# can.net
KiCad netlist of a schematic drawn in Altium Designer
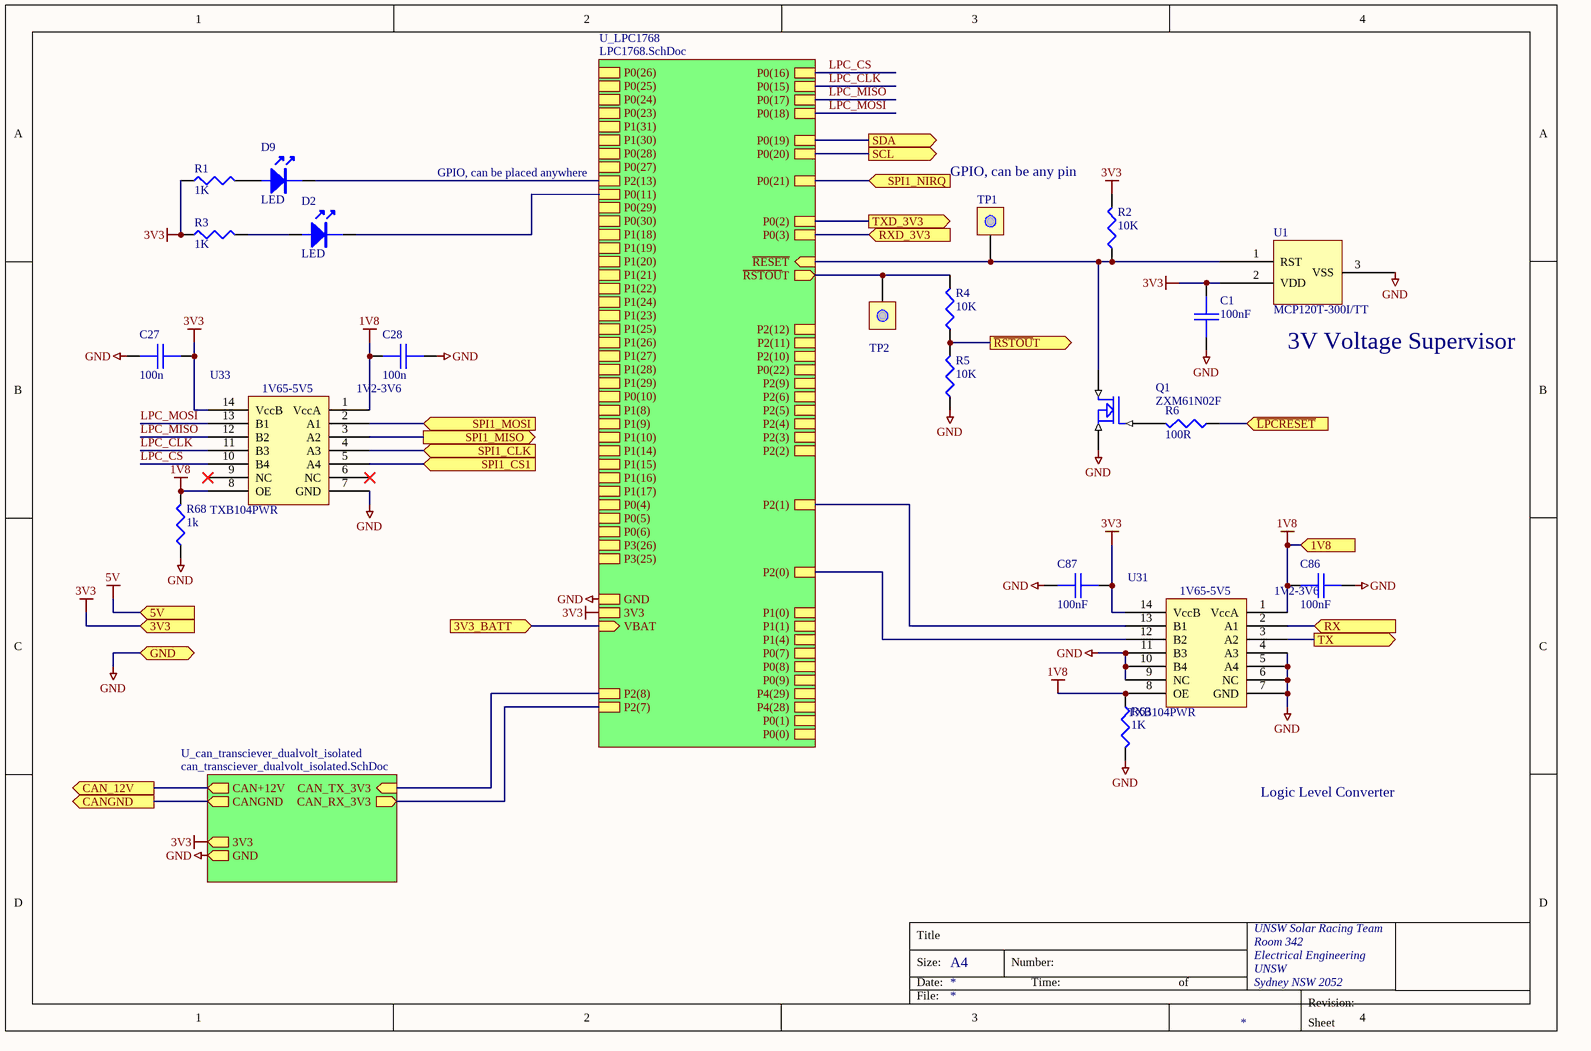
[diagram p0: can.SchDoc]

(export (version "E")
  (design (tool "Eeschema 10.0.6"))
  (components
    (comp (ref "C1")
      (value "100nF")
      (footprint "0603")
      (description "Capacitor")
      (libsource (lib "RCLDQ") (part "CAP"))
    )
    (comp (ref "C27")
      (value "100n")
      (footprint "0603")
      (description "Capacitor")
      (libsource (lib "RCLDQ") (part "CAP"))
    )
    (comp (ref "C28")
      (value "100n")
      (footprint "0603")
      (description "Capacitor")
      (libsource (lib "RCLDQ") (part "CAP"))
    )
    (comp (ref "C86")
      (value "100nF")
      (footprint "0603")
      (description "Capacitor")
      (libsource (lib "RCLDQ") (part "CAP"))
    )
    (comp (ref "C87")
      (value "100nF")
      (footprint "0603")
      (description "Capacitor")
      (libsource (lib "RCLDQ") (part "CAP"))
    )
    (comp (ref "D2") (value "LED") (footprint "0805LED") (libsource (lib "RCLDQ") (part "LED")))
    (comp (ref "D9") (value "LED") (footprint "0805LED") (libsource (lib "RCLDQ") (part "LED")))
    (comp (ref "Q1")
      (value "ZXM61N02F")
      (footprint "SOT23-3")
      (description "1.7A, 20V N-Channel Enhancement mode FET")
      (libsource (lib "RCLDQ") (part "ZXM61N02F"))
    )
    (comp (ref "R1")
      (value "1K")
      (footprint "0603")
      (description "Resistor")
      (libsource (lib "RCLDQ") (part "RES1"))
    )
    (comp (ref "R2")
      (value "10K")
      (footprint "0603")
      (description "Resistor")
      (libsource (lib "RCLDQ") (part "RES1"))
    )
    (comp (ref "R3")
      (value "1K")
      (footprint "0603")
      (description "Resistor")
      (libsource (lib "RCLDQ") (part "RES1"))
    )
    (comp (ref "R4")
      (value "10K")
      (footprint "0603")
      (description "Resistor")
      (libsource (lib "RCLDQ") (part "RES1"))
    )
    (comp (ref "R5")
      (value "10K")
      (footprint "0603")
      (description "Resistor")
      (libsource (lib "RCLDQ") (part "RES1"))
    )
    (comp (ref "R6")
      (value "100R")
      (footprint "0603")
      (description "Resistor")
      (libsource (lib "RCLDQ") (part "RES1"))
    )
    (comp (ref "R63")
      (value "1K")
      (footprint "0603")
      (description "Resistor")
      (libsource (lib "RCLDQ") (part "RES1"))
    )
    (comp (ref "R68")
      (value "1k")
      (footprint "0603")
      (description "Resistor")
      (libsource (lib "RCLDQ") (part "RES1"))
    )
    (comp (ref "TP1")
      (value "RESET")
      (footprint "TESTPOINT")
      (description "TEST POINT")
      (libsource (lib "Miscellaneous") (part "TEST"))
    )
    (comp (ref "TP2")
      (value "RSTOUT")
      (footprint "TESTPOINT")
      (description "TEST POINT")
      (libsource (lib "") (part "TEST_1"))
    )
    (comp (ref "U1")
      (value "MCP120T-300I/TT")
      (footprint "SOT23-3")
      (description "Voltage Supervisor")
      (libsource (lib "sion") (part "MCP120T"))
    )
    (comp (ref "U31")
      (value "TXB104PWR")
      (footprint "TSSOP14-L")
      (description "4 bit bidirectional auto direction sense level translator")
      (libsource (lib "sion") (part "TXB0104PWR"))
    )
    (comp (ref "U33")
      (value "TXB104PWR")
      (footprint "TSSOP14-L")
      (description "4 bit bidirectional auto direction sense level translator")
      (libsource (lib "sion") (part "TXB0104PWR"))
    )
  )
  (nets
    (net (code "6") (name "/LPC_CLK") (class "Default")
      (node (ref "U33") (pin "11") (pinfunction "B3_11") (pintype "passive"))
    )
    (net (code "7") (name "/LPC_CS") (class "Default")
      (node (ref "U33") (pin "10") (pinfunction "B4_10") (pintype "passive"))
    )
    (net (code "8") (name "/LPC_MISO") (class "Default")
      (node (ref "U33") (pin "12") (pinfunction "B2_12") (pintype "passive"))
    )
    (net (code "9") (name "/LPC_MOSI") (class "Default")
      (node (ref "U33") (pin "13") (pinfunction "B1_13") (pintype "passive"))
    )
    (net (code "19") (name "/P0(11)") (class "Default")
      (node (ref "D2") (pin "K") (pinfunction "K_K") (pintype "passive"))
    )
    (net (code "53") (name "/P2(0)") (class "Default")
      (node (ref "U31") (pin "12") (pinfunction "B2_12") (pintype "passive"))
    )
    (net (code "54") (name "/P2(1)") (class "Default")
      (node (ref "U31") (pin "13") (pinfunction "B1_13") (pintype "passive"))
    )
    (net (code "64") (name "/P2(13)") (class "Default")
      (node (ref "D9") (pin "K") (pinfunction "K_K") (pintype "passive"))
    )
    (net (code "69") (name "/RX") (class "Default")
      (node (ref "U31") (pin "2") (pinfunction "A1_2") (pintype "passive"))
    )
    (net (code "73") (name "/SPI1_CLK") (class "Default")
      (node (ref "U33") (pin "4") (pinfunction "A3_4") (pintype "passive"))
    )
    (net (code "74") (name "/SPI1_CS1") (class "Default")
      (node (ref "U33") (pin "5") (pinfunction "A4_5") (pintype "passive"))
    )
    (net (code "75") (name "/SPI1_MISO") (class "Default")
      (node (ref "U33") (pin "3") (pinfunction "A2_3") (pintype "passive"))
    )
    (net (code "76") (name "/SPI1_MOSI") (class "Default")
      (node (ref "U33") (pin "2") (pinfunction "A1_2") (pintype "passive"))
    )
    (net (code "78") (name "/TX") (class "Default")
      (node (ref "U31") (pin "3") (pinfunction "A2_3") (pintype "passive"))
    )
    (net (code "80") (name "/~{LPCRESET}") (class "Default")
      (node (ref "R6") (pin "2") (pinfunction "2_2") (pintype "passive"))
    )
    (net (code "81") (name "/~{RESET}") (class "Default")
      (node (ref "Q1") (pin "3") (pinfunction "D_3") (pintype "input"))
      (node (ref "R2") (pin "1") (pinfunction "1_1") (pintype "passive"))
      (node (ref "TP1") (pin "0") (pinfunction "TP_0") (pintype "passive"))
      (node (ref "U1") (pin "1") (pinfunction "RST_1") (pintype "passive"))
    )
    (net (code "82") (name "/~{RSTOU}T") (class "Default")
      (node (ref "R4") (pin "1") (pinfunction "1_1") (pintype "passive"))
      (node (ref "R5") (pin "2") (pinfunction "2_2") (pintype "passive"))
    )
    (net (code "83") (name "/~{RSTOU}T_1") (class "Default")
      (node (ref "R4") (pin "2") (pinfunction "2_2") (pintype "passive"))
      (node (ref "TP2") (pin "0") (pinfunction "TP_0") (pintype "passive"))
    )
    (net (code "84") (name "1V8") (class "Default")
      (node (ref "C28") (pin "1") (pinfunction "1_1") (pintype "passive"))
      (node (ref "C86") (pin "2") (pinfunction "2_2") (pintype "passive"))
      (node (ref "R63") (pin "2") (pinfunction "2_2") (pintype "passive"))
      (node (ref "R68") (pin "2") (pinfunction "2_2") (pintype "passive"))
      (node (ref "U31") (pin "1") (pinfunction "VccA_1") (pintype "power_in"))
      (node (ref "U31") (pin "8") (pinfunction "OE_8") (pintype "passive"))
      (node (ref "U33") (pin "1") (pinfunction "VccA_1") (pintype "power_in"))
      (node (ref "U33") (pin "8") (pinfunction "OE_8") (pintype "passive"))
    )
    (net (code "85") (name "3V3") (class "Default")
      (node (ref "C1") (pin "1") (pinfunction "1_1") (pintype "passive"))
      (node (ref "C27") (pin "2") (pinfunction "2_2") (pintype "passive"))
      (node (ref "C87") (pin "1") (pinfunction "1_1") (pintype "passive"))
      (node (ref "R1") (pin "1") (pinfunction "1_1") (pintype "passive"))
      (node (ref "R2") (pin "2") (pinfunction "2_2") (pintype "passive"))
      (node (ref "R3") (pin "1") (pinfunction "1_1") (pintype "passive"))
      (node (ref "U1") (pin "2") (pinfunction "VDD_2") (pintype "passive"))
      (node (ref "U31") (pin "14") (pinfunction "VccB_14") (pintype "power_in"))
      (node (ref "U33") (pin "14") (pinfunction "VccB_14") (pintype "power_in"))
    )
    (net (code "87") (name "GND") (class "Default")
      (node (ref "C1") (pin "2") (pinfunction "2_2") (pintype "passive"))
      (node (ref "C27") (pin "1") (pinfunction "1_1") (pintype "passive"))
      (node (ref "C28") (pin "2") (pinfunction "2_2") (pintype "passive"))
      (node (ref "C86") (pin "1") (pinfunction "1_1") (pintype "passive"))
      (node (ref "C87") (pin "2") (pinfunction "2_2") (pintype "passive"))
      (node (ref "Q1") (pin "2") (pinfunction "S_2") (pintype "input"))
      (node (ref "R5") (pin "1") (pinfunction "1_1") (pintype "passive"))
      (node (ref "R63") (pin "1") (pinfunction "1_1") (pintype "passive"))
      (node (ref "R68") (pin "1") (pinfunction "1_1") (pintype "passive"))
      (node (ref "U1") (pin "3") (pinfunction "VSS_3") (pintype "passive"))
      (node (ref "U31") (pin "10") (pinfunction "B4_10") (pintype "passive"))
      (node (ref "U31") (pin "11") (pinfunction "B3_11") (pintype "passive"))
      (node (ref "U31") (pin "4") (pinfunction "A3_4") (pintype "passive"))
      (node (ref "U31") (pin "5") (pinfunction "A4_5") (pintype "passive"))
      (node (ref "U31") (pin "6") (pinfunction "NC_6") (pintype "passive"))
      (node (ref "U31") (pin "7") (pinfunction "GND_7") (pintype "power_in"))
      (node (ref "U31") (pin "9") (pinfunction "NC_9") (pintype "passive"))
      (node (ref "U33") (pin "7") (pinfunction "GND_7") (pintype "power_in"))
    )
    (net (code "88") (name "Net-(D2-PadA)") (class "Default")
      (node (ref "D2") (pin "A") (pinfunction "A_A") (pintype "passive"))
      (node (ref "R3") (pin "2") (pinfunction "2_2") (pintype "passive"))
    )
    (net (code "89") (name "Net-(D9-PadA)") (class "Default")
      (node (ref "D9") (pin "A") (pinfunction "A_A") (pintype "passive"))
      (node (ref "R1") (pin "2") (pinfunction "2_2") (pintype "passive"))
    )
    (net (code "90") (name "Net-(Q1-G)") (class "Default")
      (node (ref "Q1") (pin "1") (pinfunction "G_1") (pintype "input"))
      (node (ref "R6") (pin "1") (pinfunction "1_1") (pintype "passive"))
    )
    (net (code "91") (name "unconnected-(U33-NC-Pad6)") (class "Default")
      (node (ref "U33") (pin "6") (pinfunction "NC_6") (pintype "passive+no_connect"))
    )
    (net (code "92") (name "unconnected-(U33-NC-Pad9)") (class "Default")
      (node (ref "U33") (pin "9") (pinfunction "NC_9") (pintype "passive+no_connect"))
    )
  )
)
